# Power_Discrete_-_Core.net
KiCad netlist of a schematic drawn in Altium Designer
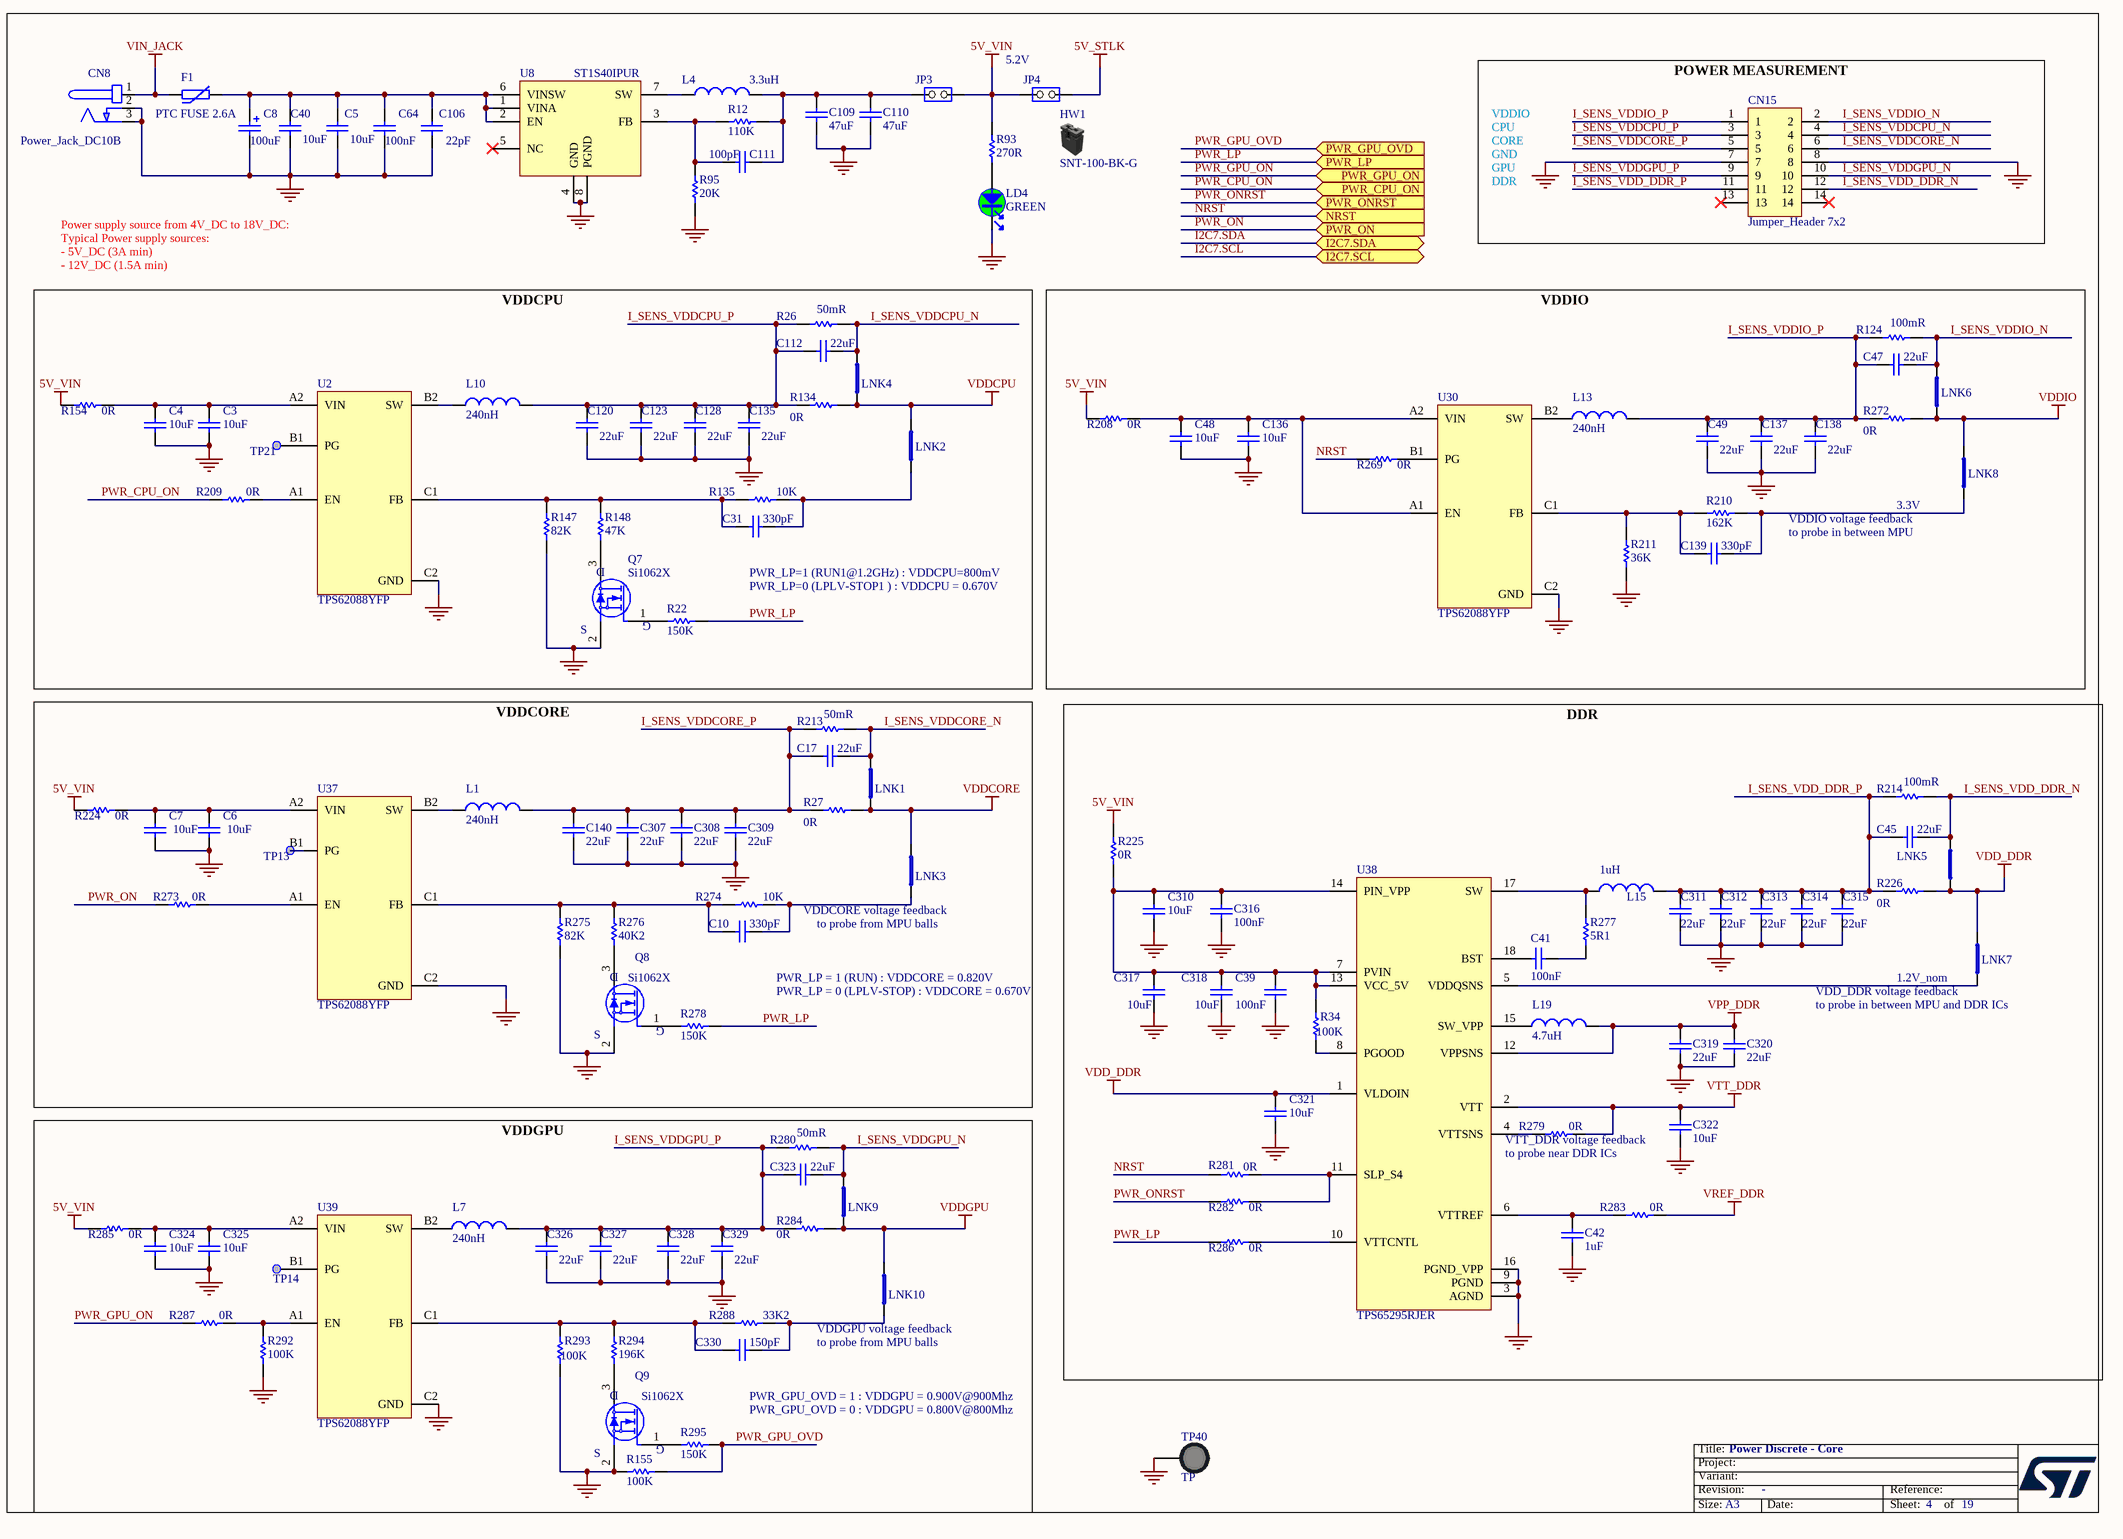
[diagram p0: Power_Discrete - Core.SchDoc]

(export (version "E")
  (design (tool "Eeschema 10.0.6"))
  (components
    (comp (ref "C3")
      (value "10uF")
      (footprint "C0603")
      (description "Capacitor, MLCC, 10uF, 10V, X5R, +/-10%, 0603, T=0,8mm")
      (fields
        (field (name "INTERNAL_PART_NUMBER") "MCD-00099")
        (field (name "MANUFACTURER_PART_NUMBER") "GRM188R61A106KE69D")
      )
      (libsource (lib "MCD_PARTS_database") (part "Capacitor"))
    )
    (comp (ref "C4")
      (value "10uF")
      (footprint "C0603")
      (description "Capacitor, MLCC, 10uF, 10V, X5R, +/-10%, 0603, T=0,8mm")
      (fields
        (field (name "INTERNAL_PART_NUMBER") "MCD-00099")
        (field (name "MANUFACTURER_PART_NUMBER") "GRM188R61A106KE69D")
      )
      (libsource (lib "MCD_PARTS_database") (part "Capacitor"))
    )
    (comp (ref "C5")
      (value "10uF")
      (footprint "C0805")
      (description "Capacitor, MLCC, 10uF, 25V, X5R, +/-10%, 0805, T=0,85mm")
      (fields (field (name "INTERNAL_PART_NUMBER") "MCD-00014") (field (name "MANUFACTURER") "YAGEO"))
      (libsource (lib "MCD_PARTS_database") (part "Capacitor"))
    )
    (comp (ref "C6")
      (value "10uF")
      (footprint "C0603")
      (description "Capacitor, MLCC, 10uF, 10V, X5R, +/-10%, 0603, T=0,8mm")
      (fields
        (field (name "INTERNAL_PART_NUMBER") "MCD-00099")
        (field (name "MANUFACTURER_PART_NUMBER") "GRM188R61A106KE69D")
      )
      (libsource (lib "MCD_PARTS_database") (part "Capacitor"))
    )
    (comp (ref "C7")
      (value "10uF")
      (footprint "C0603")
      (description "Capacitor, MLCC, 10uF, 10V, X5R, +/-10%, 0603, T=0,8mm")
      (fields
        (field (name "INTERNAL_PART_NUMBER") "MCD-00099")
        (field (name "MANUFACTURER_PART_NUMBER") "GRM188R61A106KE69D")
      )
      (libsource (lib "MCD_PARTS_database") (part "Capacitor"))
    )
    (comp (ref "C8")
      (value "100uF")
      (footprint "CPOL_WURTH_WCAP-ASLL_8X10P5")
      (description "Capacitor,Electrolytic,100uF,35V, 20%, SMT, D=8mm, T=10.5mm")
      (fields
        (field (name "INTERNAL_PART_NUMBER") "MCD-01683")
        (field (name "MANUFACTURER") "WURTH ELEKTRONIK")
      )
      (libsource (lib "MCD_PARTS_database") (part "Cap_POL_TANA"))
    )
    (comp (ref "C10")
      (value "330pF")
      (footprint "C0402")
      (description "Capacitor, MLCC, 330pF, 50V, NPO, +/-5%, 0402, T=0.5mm")
      (fields (field (name "INTERNAL_PART_NUMBER") "MCD-01579") (field (name "MANUFACTURER") "YAGEO"))
      (libsource (lib "MCD_PARTS_database") (part "Capacitor"))
    )
    (comp (ref "C17")
      (value "22uF")
      (footprint "C0603")
      (description "Capacitor, MLCC, 22uF, 6V3, X5R, +/-20%, 0603, T=0,8mm")
      (fields
        (field (name "INTERNAL_PART_NUMBER") "MCD-00100")
        (field (name "MANUFACTURER_PART_NUMBER") "GRM188R60J226MEA0J")
      )
      (libsource (lib "MCD_PARTS_database") (part "Capacitor"))
    )
    (comp (ref "C31")
      (value "330pF")
      (footprint "C0402")
      (description "Capacitor, MLCC, 330pF, 50V, NPO, +/-5%, 0402, T=0.5mm")
      (fields (field (name "INTERNAL_PART_NUMBER") "MCD-01579") (field (name "MANUFACTURER") "YAGEO"))
      (libsource (lib "MCD_PARTS_database") (part "Capacitor"))
    )
    (comp (ref "C39")
      (value "100nF")
      (footprint "C0402")
      (description "Capacitor, MLCC, 100nF, 16V, X7R, +/-10%, 0402, T=0.5mm")
      (fields (field (name "INTERNAL_PART_NUMBER") "MCD-00006") (field (name "MANUFACTURER") "YAGEO"))
      (libsource (lib "MCD_PARTS_database") (part "Capacitor"))
    )
    (comp (ref "C40")
      (value "10uF")
      (footprint "C0805")
      (description "Capacitor, MLCC, 10uF, 25V, X5R, +/-10%, 0805, T=0,85mm")
      (fields (field (name "INTERNAL_PART_NUMBER") "MCD-00014") (field (name "MANUFACTURER") "YAGEO"))
      (libsource (lib "MCD_PARTS_database") (part "Capacitor"))
    )
    (comp (ref "C41")
      (value "100nF")
      (footprint "C0402")
      (description "Capacitor, MLCC, 100nF, 16V, X7R, +/-10%, 0402, T=0.5mm")
      (fields (field (name "INTERNAL_PART_NUMBER") "MCD-00006") (field (name "MANUFACTURER") "YAGEO"))
      (libsource (lib "MCD_PARTS_database") (part "Capacitor"))
    )
    (comp (ref "C42")
      (value "1uF")
      (footprint "C0402")
      (description "Capacitor, MLCC, 1uF, 10V, X5R, +/-10%, 0402, T=0.5mm")
      (fields (field (name "INTERNAL_PART_NUMBER") "MCD-01722") (field (name "MANUFACTURER") "YAGEO"))
      (libsource (lib "MCD_PARTS_database") (part "Capacitor"))
    )
    (comp (ref "C45")
      (value "22uF")
      (footprint "C0603")
      (description "Capacitor, MLCC, 22uF, 6V3, X5R, +/-20%, 0603, T=0,8mm")
      (fields
        (field (name "INTERNAL_PART_NUMBER") "MCD-00100")
        (field (name "MANUFACTURER_PART_NUMBER") "GRM188R60J226MEA0J")
      )
      (libsource (lib "MCD_PARTS_database") (part "Capacitor"))
    )
    (comp (ref "C47")
      (value "22uF")
      (footprint "C0603")
      (description "Capacitor, MLCC, 22uF, 6V3, X5R, +/-20%, 0603, T=0,8mm")
      (fields
        (field (name "INTERNAL_PART_NUMBER") "MCD-00100")
        (field (name "MANUFACTURER_PART_NUMBER") "GRM188R60J226MEA0J")
      )
      (libsource (lib "MCD_PARTS_database") (part "Capacitor"))
    )
    (comp (ref "C48")
      (value "10uF")
      (footprint "C0603")
      (description "Capacitor, MLCC, 10uF, 10V, X5R, +/-10%, 0603, T=0,8mm")
      (fields
        (field (name "INTERNAL_PART_NUMBER") "MCD-00099")
        (field (name "MANUFACTURER_PART_NUMBER") "GRM188R61A106KE69D")
      )
      (libsource (lib "MCD_PARTS_database") (part "Capacitor"))
    )
    (comp (ref "C49")
      (value "22uF")
      (footprint "C0603")
      (description "Capacitor, MLCC, 22uF, 6V3, X5R, +/-20%, 0603, T=0,8mm")
      (fields
        (field (name "INTERNAL_PART_NUMBER") "MCD-00100")
        (field (name "MANUFACTURER_PART_NUMBER") "GRM188R60J226MEA0J")
      )
      (libsource (lib "MCD_PARTS_database") (part "Capacitor"))
    )
    (comp (ref "C64")
      (value "100nF")
      (footprint "C0805_H0P85")
      (description "Capacitor, MLCC, 100nF, 50V, X7R, 10%, 0805, T=0,85mm")
      (fields (field (name "INTERNAL_PART_NUMBER") "MCD-01525") (field (name "BMS_PART_NUMBER") "9142249"))
      (libsource (lib "MCD_PARTS_database") (part "Capacitor"))
    )
    (comp (ref "C106")
      (value "22pF")
      (footprint "C0402")
      (description "Capacitor, MLCC, 22pF, 50V, C0G, 5%, 0402, T=0,5mm")
      (fields (field (name "INTERNAL_PART_NUMBER") "MCD-01995") (field (name "MANUFACTURER") "TDK"))
      (libsource (lib "MCD_PARTS_database") (part "Capacitor"))
    )
    (comp (ref "C109")
      (value "47uF")
      (footprint "C0805")
      (description "Capacitor, MLCC, 47uF, 10V, X5R, +/-20%, 0805, T=1,25mm")
      (fields (field (name "INTERNAL_PART_NUMBER") "MCD-00204") (field (name "MANUFACTURER") "MURATA"))
      (libsource (lib "MCD_PARTS_database") (part "Capacitor"))
    )
    (comp (ref "C110")
      (value "47uF")
      (footprint "C0805")
      (description "Capacitor, MLCC, 47uF, 10V, X5R, +/-20%, 0805, T=1,25mm")
      (fields (field (name "INTERNAL_PART_NUMBER") "MCD-00204") (field (name "MANUFACTURER") "MURATA"))
      (libsource (lib "MCD_PARTS_database") (part "Capacitor"))
    )
    (comp (ref "C111")
      (value "100pF")
      (footprint "C0402")
      (description "Capacitor,MLCC,100pF,50V,NPO,+/-5%,0402,T=0,5mm")
      (fields
        (field (name "INTERNAL_PART_NUMBER") "MCD-00205")
        (field (name "MANUFACTURER_PART_NUMBER") "CC0402JRNPO9BN101")
      )
      (libsource (lib "MCD_PARTS_database") (part "Capacitor"))
    )
    (comp (ref "C112")
      (value "22uF")
      (footprint "C0603")
      (description "Capacitor, MLCC, 22uF, 6V3, X5R, +/-20%, 0603, T=0,8mm")
      (fields
        (field (name "INTERNAL_PART_NUMBER") "MCD-00100")
        (field (name "MANUFACTURER_PART_NUMBER") "GRM188R60J226MEA0J")
      )
      (libsource (lib "MCD_PARTS_database") (part "Capacitor"))
    )
    (comp (ref "C120")
      (value "22uF")
      (footprint "C0603")
      (description "Capacitor, MLCC, 22uF, 6V3, X5R, +/-20%, 0603, T=0,8mm")
      (fields
        (field (name "INTERNAL_PART_NUMBER") "MCD-00100")
        (field (name "MANUFACTURER_PART_NUMBER") "GRM188R60J226MEA0J")
      )
      (libsource (lib "MCD_PARTS_database") (part "Capacitor"))
    )
    (comp (ref "C123")
      (value "22uF")
      (footprint "C0603")
      (description "Capacitor, MLCC, 22uF, 6V3, X5R, +/-20%, 0603, T=0,8mm")
      (fields
        (field (name "INTERNAL_PART_NUMBER") "MCD-00100")
        (field (name "MANUFACTURER_PART_NUMBER") "GRM188R60J226MEA0J")
      )
      (libsource (lib "MCD_PARTS_database") (part "Capacitor"))
    )
    (comp (ref "C128")
      (value "22uF")
      (footprint "C0603")
      (description "Capacitor, MLCC, 22uF, 6V3, X5R, +/-20%, 0603, T=0,8mm")
      (fields
        (field (name "INTERNAL_PART_NUMBER") "MCD-00100")
        (field (name "MANUFACTURER_PART_NUMBER") "GRM188R60J226MEA0J")
      )
      (libsource (lib "MCD_PARTS_database") (part "Capacitor"))
    )
    (comp (ref "C135")
      (value "22uF")
      (footprint "C0603")
      (description "Capacitor, MLCC, 22uF, 6V3, X5R, +/-20%, 0603, T=0,8mm")
      (fields
        (field (name "INTERNAL_PART_NUMBER") "MCD-00100")
        (field (name "MANUFACTURER_PART_NUMBER") "GRM188R60J226MEA0J")
      )
      (libsource (lib "MCD_PARTS_database") (part "Capacitor"))
    )
    (comp (ref "C136")
      (value "10uF")
      (footprint "C0603")
      (description "Capacitor, MLCC, 10uF, 10V, X5R, +/-10%, 0603, T=0,8mm")
      (fields
        (field (name "INTERNAL_PART_NUMBER") "MCD-00099")
        (field (name "MANUFACTURER_PART_NUMBER") "GRM188R61A106KE69D")
      )
      (libsource (lib "MCD_PARTS_database") (part "Capacitor"))
    )
    (comp (ref "C137")
      (value "22uF")
      (footprint "C0603")
      (description "Capacitor, MLCC, 22uF, 6V3, X5R, +/-20%, 0603, T=0,8mm")
      (fields
        (field (name "INTERNAL_PART_NUMBER") "MCD-00100")
        (field (name "MANUFACTURER_PART_NUMBER") "GRM188R60J226MEA0J")
      )
      (libsource (lib "MCD_PARTS_database") (part "Capacitor"))
    )
    (comp (ref "C138")
      (value "22uF")
      (footprint "C0603")
      (description "Capacitor, MLCC, 22uF, 6V3, X5R, +/-20%, 0603, T=0,8mm")
      (fields
        (field (name "INTERNAL_PART_NUMBER") "MCD-00100")
        (field (name "MANUFACTURER_PART_NUMBER") "GRM188R60J226MEA0J")
      )
      (libsource (lib "MCD_PARTS_database") (part "Capacitor"))
    )
    (comp (ref "C139")
      (value "330pF")
      (footprint "C0402")
      (description "Capacitor, MLCC, 330pF, 50V, NPO, +/-5%, 0402, T=0.5mm")
      (fields (field (name "INTERNAL_PART_NUMBER") "MCD-01579") (field (name "MANUFACTURER") "YAGEO"))
      (libsource (lib "MCD_PARTS_database") (part "Capacitor"))
    )
    (comp (ref "C140")
      (value "22uF")
      (footprint "C0603")
      (description "Capacitor, MLCC, 22uF, 6V3, X5R, +/-20%, 0603, T=0,8mm")
      (fields (field (name "INTERNAL_PART_NUMBER") "MCD-00100") (field (name "MANUFACTURER") "MURATA"))
      (libsource (lib "MCD_PARTS_database") (part "Capacitor"))
    )
    (comp (ref "C307")
      (value "22uF")
      (footprint "C0603")
      (description "Capacitor, MLCC, 22uF, 6V3, X5R, +/-20%, 0603, T=0,8mm")
      (fields (field (name "INTERNAL_PART_NUMBER") "MCD-00100") (field (name "MANUFACTURER") "MURATA"))
      (libsource (lib "MCD_PARTS_database") (part "Capacitor"))
    )
    (comp (ref "C308")
      (value "22uF")
      (footprint "C0603")
      (description "Capacitor, MLCC, 22uF, 6V3, X5R, +/-20%, 0603, T=0,8mm")
      (fields
        (field (name "INTERNAL_PART_NUMBER") "MCD-00100")
        (field (name "MANUFACTURER_PART_NUMBER") "GRM188R60J226MEA0J")
      )
      (libsource (lib "MCD_PARTS_database") (part "Capacitor"))
    )
    (comp (ref "C309")
      (value "22uF")
      (footprint "C0603")
      (description "Capacitor, MLCC, 22uF, 6V3, X5R, +/-20%, 0603, T=0,8mm")
      (fields
        (field (name "INTERNAL_PART_NUMBER") "MCD-00100")
        (field (name "MANUFACTURER_PART_NUMBER") "GRM188R60J226MEA0J")
      )
      (libsource (lib "MCD_PARTS_database") (part "Capacitor"))
    )
    (comp (ref "C310")
      (value "10uF")
      (footprint "C0603")
      (description "Capacitor, MLCC, 10uF, 10V, X5R, +/-10%, 0603, T=0,8mm")
      (fields
        (field (name "INTERNAL_PART_NUMBER") "MCD-00099")
        (field (name "MANUFACTURER_PART_NUMBER") "GRM188R61A106KE69D")
      )
      (libsource (lib "MCD_PARTS_database") (part "Capacitor"))
    )
    (comp (ref "C311")
      (value "22uF")
      (footprint "C0603")
      (description "Capacitor, MLCC, 22uF, 6V3, X5R, +/-20%, 0603, T=0,8mm")
      (fields
        (field (name "INTERNAL_PART_NUMBER") "MCD-00100")
        (field (name "MANUFACTURER_PART_NUMBER") "GRM188R60J226MEA0J")
      )
      (libsource (lib "MCD_PARTS_database") (part "Capacitor"))
    )
    (comp (ref "C312")
      (value "22uF")
      (footprint "C0603")
      (description "Capacitor, MLCC, 22uF, 6V3, X5R, +/-20%, 0603, T=0,8mm")
      (fields
        (field (name "INTERNAL_PART_NUMBER") "MCD-00100")
        (field (name "MANUFACTURER_PART_NUMBER") "GRM188R60J226MEA0J")
      )
      (libsource (lib "MCD_PARTS_database") (part "Capacitor"))
    )
    (comp (ref "C313")
      (value "22uF")
      (footprint "C0603")
      (description "Capacitor, MLCC, 22uF, 6V3, X5R, +/-20%, 0603, T=0,8mm")
      (fields
        (field (name "INTERNAL_PART_NUMBER") "MCD-00100")
        (field (name "MANUFACTURER_PART_NUMBER") "GRM188R60J226MEA0J")
      )
      (libsource (lib "MCD_PARTS_database") (part "Capacitor"))
    )
    (comp (ref "C314")
      (value "22uF")
      (footprint "C0603")
      (description "Capacitor, MLCC, 22uF, 6V3, X5R, +/-20%, 0603, T=0,8mm")
      (fields
        (field (name "INTERNAL_PART_NUMBER") "MCD-00100")
        (field (name "MANUFACTURER_PART_NUMBER") "GRM188R60J226MEA0J")
      )
      (libsource (lib "MCD_PARTS_database") (part "Capacitor"))
    )
    (comp (ref "C315")
      (value "22uF")
      (footprint "C0603")
      (description "Capacitor, MLCC, 22uF, 6V3, X5R, +/-20%, 0603, T=0,8mm")
      (fields
        (field (name "INTERNAL_PART_NUMBER") "MCD-00100")
        (field (name "MANUFACTURER_PART_NUMBER") "GRM188R60J226MEA0J")
      )
      (libsource (lib "MCD_PARTS_database") (part "Capacitor"))
    )
    (comp (ref "C316")
      (value "100nF")
      (footprint "C0402")
      (description "Capacitor, MLCC, 100nF, 16V, X7R, +/-10%, 0402, T=0.5mm")
      (fields (field (name "INTERNAL_PART_NUMBER") "MCD-00006") (field (name "MANUFACTURER") "YAGEO"))
      (libsource (lib "MCD_PARTS_database") (part "Capacitor"))
    )
    (comp (ref "C317")
      (value "10uF")
      (footprint "C0603")
      (description "Capacitor, MLCC, 10uF, 10V, X5R, +/-10%, 0603, T=0,8mm")
      (fields
        (field (name "INTERNAL_PART_NUMBER") "MCD-00099")
        (field (name "MANUFACTURER_PART_NUMBER") "GRM188R61A106KE69D")
      )
      (libsource (lib "MCD_PARTS_database") (part "Capacitor"))
    )
    (comp (ref "C318")
      (value "10uF")
      (footprint "C0603")
      (description "Capacitor, MLCC, 10uF, 10V, X5R, +/-10%, 0603, T=0,8mm")
      (fields
        (field (name "INTERNAL_PART_NUMBER") "MCD-00099")
        (field (name "MANUFACTURER_PART_NUMBER") "GRM188R61A106KE69D")
      )
      (libsource (lib "MCD_PARTS_database") (part "Capacitor"))
    )
    (comp (ref "C319")
      (value "22uF")
      (footprint "C0603")
      (description "Capacitor, MLCC, 22uF, 6V3, X5R, +/-20%, 0603, T=0,8mm")
      (fields
        (field (name "INTERNAL_PART_NUMBER") "MCD-00100")
        (field (name "MANUFACTURER_PART_NUMBER") "GRM188R60J226MEA0J")
      )
      (libsource (lib "MCD_PARTS_database") (part "Capacitor"))
    )
    (comp (ref "C320")
      (value "22uF")
      (footprint "C0603")
      (description "Capacitor, MLCC, 22uF, 6V3, X5R, +/-20%, 0603, T=0,8mm")
      (fields
        (field (name "INTERNAL_PART_NUMBER") "MCD-00100")
        (field (name "MANUFACTURER_PART_NUMBER") "GRM188R60J226MEA0J")
      )
      (libsource (lib "MCD_PARTS_database") (part "Capacitor"))
    )
    (comp (ref "C321")
      (value "10uF")
      (footprint "C0603")
      (description "Capacitor, MLCC, 10uF, 10V, X5R, +/-10%, 0603, T=0,8mm")
      (fields
        (field (name "INTERNAL_PART_NUMBER") "MCD-00099")
        (field (name "MANUFACTURER_PART_NUMBER") "GRM188R61A106KE69D")
      )
      (libsource (lib "MCD_PARTS_database") (part "Capacitor"))
    )
    (comp (ref "C322")
      (value "10uF")
      (footprint "C0603")
      (description "Capacitor, MLCC, 10uF, 10V, X5R, +/-10%, 0603, T=0,8mm")
      (fields
        (field (name "INTERNAL_PART_NUMBER") "MCD-00099")
        (field (name "MANUFACTURER_PART_NUMBER") "GRM188R61A106KE69D")
      )
      (libsource (lib "MCD_PARTS_database") (part "Capacitor"))
    )
    (comp (ref "C323")
      (value "22uF")
      (footprint "C0603")
      (description "Capacitor, MLCC, 22uF, 6V3, X5R, +/-20%, 0603, T=0,8mm")
      (fields
        (field (name "INTERNAL_PART_NUMBER") "MCD-00100")
        (field (name "MANUFACTURER_PART_NUMBER") "GRM188R60J226MEA0J")
      )
      (libsource (lib "MCD_PARTS_database") (part "Capacitor"))
    )
    (comp (ref "C324")
      (value "10uF")
      (footprint "C0603")
      (description "Capacitor, MLCC, 10uF, 10V, X5R, +/-10%, 0603, T=0,8mm")
      (fields
        (field (name "INTERNAL_PART_NUMBER") "MCD-00099")
        (field (name "MANUFACTURER_PART_NUMBER") "GRM188R61A106KE69D")
      )
      (libsource (lib "MCD_PARTS_database") (part "Capacitor"))
    )
    (comp (ref "C325")
      (value "10uF")
      (footprint "C0603")
      (description "Capacitor, MLCC, 10uF, 10V, X5R, +/-10%, 0603, T=0,8mm")
      (fields
        (field (name "INTERNAL_PART_NUMBER") "MCD-00099")
        (field (name "MANUFACTURER_PART_NUMBER") "GRM188R61A106KE69D")
      )
      (libsource (lib "MCD_PARTS_database") (part "Capacitor"))
    )
    (comp (ref "C326")
      (value "22uF")
      (footprint "C0603")
      (description "Capacitor, MLCC, 22uF, 6V3, X5R, +/-20%, 0603, T=0,8mm")
      (fields
        (field (name "INTERNAL_PART_NUMBER") "MCD-00100")
        (field (name "MANUFACTURER_PART_NUMBER") "GRM188R60J226MEA0J")
      )
      (libsource (lib "MCD_PARTS_database") (part "Capacitor"))
    )
    (comp (ref "C327")
      (value "22uF")
      (footprint "C0603")
      (description "Capacitor, MLCC, 22uF, 6V3, X5R, +/-20%, 0603, T=0,8mm")
      (fields
        (field (name "INTERNAL_PART_NUMBER") "MCD-00100")
        (field (name "MANUFACTURER_PART_NUMBER") "GRM188R60J226MEA0J")
      )
      (libsource (lib "MCD_PARTS_database") (part "Capacitor"))
    )
    (comp (ref "C328")
      (value "22uF")
      (footprint "C0603")
      (description "Capacitor, MLCC, 22uF, 6V3, X5R, +/-20%, 0603, T=0,8mm")
      (fields
        (field (name "INTERNAL_PART_NUMBER") "MCD-00100")
        (field (name "MANUFACTURER_PART_NUMBER") "GRM188R60J226MEA0J")
      )
      (libsource (lib "MCD_PARTS_database") (part "Capacitor"))
    )
    (comp (ref "C329")
      (value "22uF")
      (footprint "C0603")
      (description "Capacitor, MLCC, 22uF, 6V3, X5R, +/-20%, 0603, T=0,8mm")
      (fields
        (field (name "INTERNAL_PART_NUMBER") "MCD-00100")
        (field (name "MANUFACTURER_PART_NUMBER") "GRM188R60J226MEA0J")
      )
      (libsource (lib "MCD_PARTS_database") (part "Capacitor"))
    )
    (comp (ref "C330")
      (value "150pF")
      (footprint "C0402")
      (description "Capacitor, MLCC, 150pF, 50V, NPO, +/-5%, 0402, T=0.5mm")
      (fields (field (name "INTERNAL_PART_NUMBER") "MCD-00672") (field (name "MANUFACTURER") "YAGEO"))
      (libsource (lib "MCD_PARTS_database") (part "Capacitor"))
    )
    (comp (ref "CN8")
      (value "Power_Jack_DC10B")
      (footprint "CON_DC-POWER-SOCKET_CLIFF_FC68149_DC10B")
      (description "DC-Power-Jack, 2.5mm, 5A, RA, TH")
      (fields (field (name "INTERNAL_PART_NUMBER") "MCD-00173") (field (name "BMS_PART_NUMBER") "9087803"))
      (libsource (lib "MCD_PARTS_database") (part "Power_Jack_DC10B"))
    )
    (comp (ref "CN15")
      (value "Jumper_Header 7x2")
      (footprint "CON_SAMTEC_TSW-107-07-X-D")
      (description "Header, 7x2, 2,54mm, VR, TH, Height 5.84mm/2.54mm")
      (fields (field (name "INTERNAL_PART_NUMBER") "MCD-02123") (field (name "MANUFACTURER") "SAMTEC"))
      (libsource (lib "MCD_PARTS_database") (part "Header 7x2"))
    )
    (comp (ref "F1")
      (value "PTC FUSE 2.6A")
      (footprint "PTC_BEL-FUSE_1812_0ZCG0260FF2C")
      (description "SMD, PTC resettable fuse, IH:2.6A, IT:5A, Vdc_max:8V, Rmax:47mohm, BELFUSE")
      (fields (field (name "INTERNAL_PART_NUMBER") "MCD-00624") (field (name "MANUFACTURER") "BELFUSE"))
      (libsource (lib "MCD_PARTS_database") (part "0ZCG0260FF2C"))
    )
    (comp (ref "HW1")
      (value "SNT-100-BK-G")
      (description "SHUNT 2.54mm BLACK")
      (fields (field (name "INTERNAL_PART_NUMBER") "MCD-00043") (field (name "MANUFACTURER") "SAMTEC"))
      (libsource (lib "MCD_PARTS_database") (part "Shunt Black 2.54mm"))
    )
    (comp (ref "JP3")
      (value "Jumper_Header 2x1")
      (footprint "CON_SAMTEC_TSW-102-07-G-S")
      (description "Header, 2x1, 2.54mm, VR, TH, T=5.84mm/2.54mm")
      (fields (field (name "INTERNAL_PART_NUMBER") "MCD-00045") (field (name "MANUFACTURER") "SAMTEC"))
      (libsource (lib "MCD_PARTS_database") (part "Jumper_Header 2x1"))
    )
    (comp (ref "JP4")
      (value "Jumper_Header 2x1")
      (footprint "CON_SAMTEC_TSW-102-07-G-S")
      (description "Header, 2x1, 2.54mm, VR, TH, T=5.84mm/2.54mm")
      (fields (field (name "INTERNAL_PART_NUMBER") "MCD-00045") (field (name "MANUFACTURER") "SAMTEC"))
      (libsource (lib "MCD_PARTS_database") (part "Jumper_Header 2x1"))
    )
    (comp (ref "L1")
      (value "240nH")
      (footprint "IND_MURATA_DFE201612P")
      (description "Inductor, 240nH, +/-20%, 4.4A, 23mR, 0806, T=1.2mm")
      (fields (field (name "INTERNAL_PART_NUMBER") "MCD-02477") (field (name "MANUFACTURER") "MURATA"))
      (libsource (lib "MCD_PARTS_database") (part "Inductor"))
    )
    (comp (ref "L4")
      (value "3.3uH")
      (footprint "IND_5040_WURTH_74404054033")
      (description "Fixed Inductors WE-LQS 5040 3.3uH 3.4A 24mOhm")
      (fields
        (field (name "INTERNAL_PART_NUMBER") "MCD-02220")
        (field (name "MANUFACTURER") "WURTH ELEKTRONIK")
      )
      (libsource (lib "MCD_PARTS_database") (part "Inductor"))
    )
    (comp (ref "L7")
      (value "240nH")
      (footprint "IND_MURATA_DFE201612P")
      (description "Inductor, 240nH, +/-20%, 4.4A, 23mR, 0806, T=1.2mm")
      (fields (field (name "INTERNAL_PART_NUMBER") "MCD-02477") (field (name "MANUFACTURER") "MURATA"))
      (libsource (lib "MCD_PARTS_database") (part "Inductor"))
    )
    (comp (ref "L10")
      (value "240nH")
      (footprint "IND_MURATA_DFE201612P")
      (description "Inductor, 240nH, +/-20%, 4.4A, 23mR, 0806, T=1.2mm")
      (fields (field (name "INTERNAL_PART_NUMBER") "MCD-02477") (field (name "MANUFACTURER") "MURATA"))
      (libsource (lib "MCD_PARTS_database") (part "Inductor"))
    )
    (comp (ref "L13")
      (value "240nH")
      (footprint "IND_MURATA_DFE201612P")
      (description "Inductor, 240nH, +/-20%, 4.4A, 23mR, 0806, T=1.2mm")
      (fields (field (name "INTERNAL_PART_NUMBER") "MCD-02477") (field (name "MANUFACTURER") "MURATA"))
      (libsource (lib "MCD_PARTS_database") (part "Inductor"))
    )
    (comp (ref "L15")
      (value "1uH")
      (footprint "IND_4025_WURTH_74404043010A")
      (description "SMD Power Inductors WE-LQS 1uH 4.9A 14mOhms")
      (fields
        (field (name "INTERNAL_PART_NUMBER") "MCD-01555")
        (field (name "MANUFACTURER_PART_NUMBER") "74404043010A")
      )
      (libsource (lib "MCD_PARTS_database") (part "Inductor"))
    )
    (comp (ref "L19")
      (value "4.7uH")
      (footprint "IND_4025_WURTH_74404043047A")
      (description "Inductor, 4.7uH, +/-20%, 4.9A, 0R014, 4x4mm, T=2.5mm")
      (fields
        (field (name "INTERNAL_PART_NUMBER") "MCD-02490")
        (field (name "MANUFACTURER") "WURTH ELEKTRONIK")
      )
      (libsource (lib "MCD_PARTS_database") (part "Inductor"))
    )
    (comp (ref "LD4")
      (value "GREEN")
      (footprint "LED_0603_OSRAM_LG-Q396-PS-35_GREEN_1A2K_H0P4")
      (description "LED Green, 0603 SMD, Forward Voltage Typ=2V, Max=2.5V")
      (fields
        (field (name "INTERNAL_PART_NUMBER") "MCD-00588")
        (field (name "MANUFACTURER_PART_NUMBER") "LG Q396-PS-35")
        (field (name "PROVIDED_BY") "SUBCO")
      )
      (libsource (lib "MCD_PARTS_database") (part "LED_green"))
    )
    (comp (ref "LNK1")
      (value "link_200")
      (footprint "LINK200")
      (description "link 0.2mm")
      (libsource (lib "MCD_Temp_LBE") (part "link_200"))
    )
    (comp (ref "LNK2")
      (value "link_200")
      (footprint "LINK200")
      (description "link 0.2mm")
      (libsource (lib "MCD_Temp_LBE") (part "link_200"))
    )
    (comp (ref "LNK3")
      (value "link_200")
      (footprint "LINK200")
      (description "link 0.2mm")
      (libsource (lib "MCD_Temp_LBE") (part "link_200"))
    )
    (comp (ref "LNK4")
      (value "link_200")
      (footprint "LINK200")
      (description "link 0.2mm")
      (libsource (lib "MCD_Temp_LBE") (part "link_200"))
    )
    (comp (ref "LNK5")
      (value "link_200")
      (footprint "LINK200")
      (description "link 0.2mm")
      (libsource (lib "MCD_Temp_LBE") (part "link_200"))
    )
    (comp (ref "LNK6")
      (value "link_200")
      (footprint "LINK200")
      (description "link 0.2mm")
      (libsource (lib "MCD_Temp_LBE") (part "link_200"))
    )
    (comp (ref "LNK7")
      (value "link_200")
      (footprint "LINK200")
      (description "link 0.2mm")
      (libsource (lib "MCD_Temp_LBE") (part "link_200"))
    )
    (comp (ref "LNK8")
      (value "link_200")
      (footprint "LINK200")
      (description "link 0.2mm")
      (libsource (lib "MCD_Temp_LBE") (part "link_200"))
    )
    (comp (ref "LNK9")
      (value "link_200")
      (footprint "LINK200")
      (description "link 0.2mm")
      (libsource (lib "MCD_Temp_LBE") (part "link_200"))
    )
    (comp (ref "LNK10")
      (value "link_200")
      (footprint "LINK200")
      (description "link 0.2mm")
      (libsource (lib "MCD_Temp_LBE") (part "link_200"))
    )
    (comp (ref "Q7")
      (value "Si1062X")
      (footprint "MOS_SC89-3L")
      (description "MOSFET N-CH 20V SC-89")
      (fields (field (name "INTERNAL_PART_NUMBER") "MCD-02221") (field (name "MANUFACTURER") "VISHAY"))
      (libsource (lib "MCD_PARTS_database") (part "MOSFET_N-CHANNEL"))
    )
    (comp (ref "Q8")
      (value "Si1062X")
      (footprint "MOS_SC89-3L")
      (description "MOSFET N-CH 20V SC-89")
      (fields (field (name "INTERNAL_PART_NUMBER") "MCD-02221") (field (name "MANUFACTURER") "VISHAY"))
      (libsource (lib "MCD_PARTS_database") (part "MOSFET_N-CHANNEL"))
    )
    (comp (ref "Q9")
      (value "Si1062X")
      (footprint "MOS_SC89-3L")
      (description "MOSFET N-CH 20V SC-89")
      (fields (field (name "INTERNAL_PART_NUMBER") "MCD-02221") (field (name "MANUFACTURER") "VISHAY"))
      (libsource (lib "MCD_PARTS_database") (part "MOSFET_N-CHANNEL"))
    )
    (comp (ref "R12")
      (value "110K")
      (footprint "R0402")
      (description "Resistor,110K,0402,1%,1/16W")
      (fields
        (field (name "INTERNAL_PART_NUMBER") "MCD-00367")
        (field (name "MANUFACTURER_PART_NUMBER") "RC0402FR-07110KL")
      )
      (libsource (lib "MCD_PARTS_database") (part "Resistor"))
    )
    (comp (ref "R22")
      (value "150K")
      (footprint "R0402")
      (description "Resistor,150K,0402,1%,1/16W")
      (fields
        (field (name "INTERNAL_PART_NUMBER") "MCD-00165")
        (field (name "MANUFACTURER_PART_NUMBER") "RC0402FR-07150KL")
      )
      (libsource (lib "MCD_PARTS_database") (part "Resistor"))
    )
    (comp (ref "R26")
      (value "50mR")
      (footprint "R0603")
      (description "Resistor,50moHm,0603,1%,1/3W, T=0.55mm")
      (fields (field (name "INTERNAL_PART_NUMBER") "MCD-02233") (field (name "MANUFACTURER") "PANASONIC"))
      (libsource (lib "MCD_PARTS_database") (part "Resistor"))
    )
    (comp (ref "R27")
      (value "0R")
      (footprint "R0603")
      (description "Resistor,0R,0603,ULO")
      (fields
        (field (name "INTERNAL_PART_NUMBER") "MCD-00181")
        (field (name "MANUFACTURER_PART_NUMBER") "PMR03EZPJ000")
        (field (name "PROVIDED_BY") "SUBCO")
      )
      (libsource (lib "MCD_PARTS_database") (part "Resistor"))
    )
    (comp (ref "R34")
      (value "100K")
      (footprint "R0402")
      (description "Resistor,100K,0402,1%,1/16W")
      (fields (field (name "INTERNAL_PART_NUMBER") "MCD-00059") (field (name "MANUFACTURER") "YAGEO"))
      (libsource (lib "MCD_PARTS_database") (part "Resistor"))
    )
    (comp (ref "R93")
      (value "270R")
      (footprint "R0402")
      (description "Resistor,270R,0402,1%,1/16W")
      (fields
        (field (name "INTERNAL_PART_NUMBER") "MCD-00441")
        (field (name "MANUFACTURER_PART_NUMBER") "RC0402FR-07270RL")
        (field (name "PROVIDED_BY") "SUBCO")
      )
      (libsource (lib "MCD_PARTS_database") (part "Resistor"))
    )
    (comp (ref "R95")
      (value "20K")
      (footprint "R0402")
      (description "Resistor,20K,0402,1%,1/16W")
      (fields (field (name "INTERNAL_PART_NUMBER") "MCD-00421") (field (name "MANUFACTURER") "YAGEO"))
      (libsource (lib "MCD_PARTS_database") (part "Resistor"))
    )
    (comp (ref "R124")
      (value "100mR")
      (footprint "R0603")
      (description "Resistor,100moHm,0603,1%,1/3W")
      (fields (field (name "INTERNAL_PART_NUMBER") "MCD-02234") (field (name "MANUFACTURER") "PANASONIC"))
      (libsource (lib "MCD_PARTS_database") (part "Resistor"))
    )
    (comp (ref "R134")
      (value "0R")
      (footprint "R0603")
      (description "Resistor,0R,0603,ULO")
      (fields
        (field (name "INTERNAL_PART_NUMBER") "MCD-00181")
        (field (name "MANUFACTURER_PART_NUMBER") "PMR03EZPJ000")
        (field (name "PROVIDED_BY") "SUBCO")
      )
      (libsource (lib "MCD_PARTS_database") (part "Resistor"))
    )
    (comp (ref "R135")
      (value "10K")
      (footprint "R0402")
      (description "Resistor,10K,0402,1%,1/16W")
      (fields (field (name "INTERNAL_PART_NUMBER") "MCD-00053") (field (name "BMS_PART_NUMBER") "9131590"))
      (libsource (lib "MCD_PARTS_database") (part "Resistor"))
    )
    (comp (ref "R147")
      (value "82K")
      (footprint "R0402")
      (description "Resistor, 82K, 0402, +/-1%, 1/16W")
      (fields (field (name "INTERNAL_PART_NUMBER") "MCD-00531") (field (name "MANUFACTURER") "YAGEO"))
      (libsource (lib "MCD_PARTS_database") (part "Resistor"))
    )
    (comp (ref "R148")
      (value "47K")
      (footprint "R0402")
      (description "Resistor, 47K, 0402, +/-1%, 1/16W")
      (fields (field (name "INTERNAL_PART_NUMBER") "MCD-00063") (field (name "MANUFACTURER") "YAGEO"))
      (libsource (lib "MCD_PARTS_database") (part "Resistor"))
    )
    (comp (ref "R154")
      (value "0R")
      (footprint "R0603")
      (description "Resistor,0R,0603,5%,1/10W")
      (fields
        (field (name "INTERNAL_PART_NUMBER") "MCD-00056")
        (field (name "MANUFACTURER_PART_NUMBER") "RC0603JR-070RL")
      )
      (libsource (lib "MCD_PARTS_database") (part "Resistor"))
    )
    (comp (ref "R155")
      (value "100K")
      (footprint "R0402")
      (description "Resistor, 100K, 0402, +/-1%, 1/16W")
      (fields (field (name "INTERNAL_PART_NUMBER") "MCD-00059") (field (name "MANUFACTURER") "YAGEO"))
      (libsource (lib "MCD_PARTS_database") (part "Resistor"))
    )
    (comp (ref "R208")
      (value "0R")
      (footprint "R0603")
      (description "Resistor,0R,0603,5%,1/10W")
      (fields
        (field (name "INTERNAL_PART_NUMBER") "MCD-00056")
        (field (name "MANUFACTURER_PART_NUMBER") "RC0603JR-070RL")
      )
      (libsource (lib "MCD_PARTS_database") (part "Resistor"))
    )
    (comp (ref "R209")
      (value "0R")
      (footprint "R0402")
      (description "Resistor,0R,0402,5%,1/16W")
      (fields
        (field (name "INTERNAL_PART_NUMBER") "MCD-00052")
        (field (name "MANUFACTURER_PART_NUMBER") "RC0402JR-070RL")
      )
      (libsource (lib "MCD_PARTS_database") (part "Resistor"))
    )
    (comp (ref "R210")
      (value "162K")
      (footprint "R0402")
      (description "Resistor,162K,0402,1%,1/16W")
      (fields (field (name "INTERNAL_PART_NUMBER") "MCD-02482") (field (name "MANUFACTURER") "YAGEO"))
      (libsource (lib "MCD_PARTS_database") (part "Resistor"))
    )
    (comp (ref "R211")
      (value "36K")
      (footprint "R0402")
      (description "Resistor, 36K, 0402, 1%, 1/16W")
      (fields (field (name "INTERNAL_PART_NUMBER") "MCD-00069") (field (name "MANUFACTURER") "YAGEO"))
      (libsource (lib "MCD_PARTS_database") (part "Resistor"))
    )
    (comp (ref "R213")
      (value "50mR")
      (footprint "R0603")
      (description "Resistor,50moHm,0603,1%,1/3W, T=0.55mm")
      (fields (field (name "INTERNAL_PART_NUMBER") "MCD-02233") (field (name "MANUFACTURER") "PANASONIC"))
      (libsource (lib "MCD_PARTS_database") (part "Resistor"))
    )
    (comp (ref "R214")
      (value "100mR")
      (footprint "R0603")
      (description "Resistor,100moHm,0603,1%,1/3W")
      (fields (field (name "INTERNAL_PART_NUMBER") "MCD-02234") (field (name "MANUFACTURER") "PANASONIC"))
      (libsource (lib "MCD_PARTS_database") (part "Resistor"))
    )
    (comp (ref "R224")
      (value "0R")
      (footprint "R0603")
      (description "Resistor,0R,0603,5%,1/10W")
      (fields
        (field (name "INTERNAL_PART_NUMBER") "MCD-00056")
        (field (name "MANUFACTURER_PART_NUMBER") "RC0603JR-070RL")
      )
      (libsource (lib "MCD_PARTS_database") (part "Resistor"))
    )
    (comp (ref "R225")
      (value "0R")
      (footprint "R0603")
      (description "Resistor,0R,0603,5%,1/10W")
      (fields
        (field (name "INTERNAL_PART_NUMBER") "MCD-00056")
        (field (name "MANUFACTURER_PART_NUMBER") "RC0603JR-070RL")
      )
      (libsource (lib "MCD_PARTS_database") (part "Resistor"))
    )
    (comp (ref "R226")
      (value "0R")
      (footprint "R0603")
      (description "Resistor,0R,0603,ULO")
      (fields
        (field (name "INTERNAL_PART_NUMBER") "MCD-00181")
        (field (name "MANUFACTURER_PART_NUMBER") "PMR03EZPJ000")
        (field (name "PROVIDED_BY") "SUBCO")
      )
      (libsource (lib "MCD_PARTS_database") (part "Resistor"))
    )
    (comp (ref "R269")
      (value "0R")
      (footprint "R0603")
      (description "Resistor,0R,0603,5%,1/10W")
      (fields
        (field (name "INTERNAL_PART_NUMBER") "MCD-00056")
        (field (name "MANUFACTURER_PART_NUMBER") "RC0603JR-070RL")
      )
      (libsource (lib "MCD_PARTS_database") (part "Resistor"))
    )
    (comp (ref "R272")
      (value "0R")
      (footprint "R0603")
      (description "Resistor,0R,0603,ULO")
      (fields
        (field (name "INTERNAL_PART_NUMBER") "MCD-00181")
        (field (name "MANUFACTURER_PART_NUMBER") "PMR03EZPJ000")
        (field (name "PROVIDED_BY") "SUBCO")
      )
      (libsource (lib "MCD_PARTS_database") (part "Resistor"))
    )
    (comp (ref "R273")
      (value "0R")
      (footprint "R0402")
      (description "Resistor,0R,0402,5%,1/16W")
      (fields
        (field (name "INTERNAL_PART_NUMBER") "MCD-00052")
        (field (name "MANUFACTURER_PART_NUMBER") "RC0402JR-070RL")
      )
      (libsource (lib "MCD_PARTS_database") (part "Resistor"))
    )
    (comp (ref "R274")
      (value "10K")
      (footprint "R0402")
      (description "Resistor,10K,0402,1%,1/16W")
      (fields (field (name "INTERNAL_PART_NUMBER") "MCD-00053") (field (name "BMS_PART_NUMBER") "9131590"))
      (libsource (lib "MCD_PARTS_database") (part "Resistor"))
    )
    (comp (ref "R275")
      (value "82K")
      (footprint "R0402")
      (description "Resistor, 82K, 0402, +/-1%, 1/16W")
      (fields (field (name "INTERNAL_PART_NUMBER") "MCD-00531") (field (name "MANUFACTURER") "YAGEO"))
      (libsource (lib "MCD_PARTS_database") (part "Resistor"))
    )
    (comp (ref "R276")
      (value "40K2")
      (footprint "R0402")
      (description "Resistor, 40K2, 0402, +/-1%, 1/16W")
      (fields (field (name "INTERNAL_PART_NUMBER") "MCD-02479") (field (name "MANUFACTURER") "YAGEO"))
      (libsource (lib "MCD_PARTS_database") (part "Resistor"))
    )
    (comp (ref "R277")
      (value "5R1")
      (footprint "R0402")
      (description "Resistor, 5R1, 0402, +/-1%, 1/16W")
      (fields (field (name "INTERNAL_PART_NUMBER") "MCD-01516") (field (name "MANUFACTURER") "YAGEO"))
      (libsource (lib "MCD_PARTS_database") (part "Resistor"))
    )
    (comp (ref "R278")
      (value "150K")
      (footprint "R0402")
      (description "Resistor,150K,0402,1%,1/16W")
      (fields
        (field (name "INTERNAL_PART_NUMBER") "MCD-00165")
        (field (name "MANUFACTURER_PART_NUMBER") "RC0402FR-07150KL")
      )
      (libsource (lib "MCD_PARTS_database") (part "Resistor"))
    )
    (comp (ref "R279")
      (value "0R")
      (footprint "R0402")
      (description "Resistor,0R,0402,5%,1/16W")
      (fields
        (field (name "INTERNAL_PART_NUMBER") "MCD-00052")
        (field (name "MANUFACTURER_PART_NUMBER") "RC0402JR-070RL")
      )
      (libsource (lib "MCD_PARTS_database") (part "Resistor"))
    )
    (comp (ref "R280")
      (value "50mR")
      (footprint "R0603")
      (description "Resistor,50moHm,0603,1%,1/3W, T=0.55mm")
      (fields (field (name "INTERNAL_PART_NUMBER") "MCD-02233") (field (name "MANUFACTURER") "PANASONIC"))
      (libsource (lib "MCD_PARTS_database") (part "Resistor"))
    )
    (comp (ref "R281")
      (value "0R")
      (footprint "R0402")
      (description "Resistor,0R,0402,5%,1/16W")
      (fields
        (field (name "INTERNAL_PART_NUMBER") "MCD-00052")
        (field (name "MANUFACTURER_PART_NUMBER") "RC0402JR-070RL")
      )
      (libsource (lib "MCD_PARTS_database") (part "Resistor"))
    )
    (comp (ref "R282")
      (value "0R")
      (footprint "R0402")
      (description "Resistor,0R,0402,5%,1/16W")
      (fields
        (field (name "INTERNAL_PART_NUMBER") "MCD-00052")
        (field (name "MANUFACTURER_PART_NUMBER") "RC0402JR-070RL")
      )
      (libsource (lib "MCD_PARTS_database") (part "Resistor"))
    )
    (comp (ref "R283")
      (value "0R")
      (footprint "R0402")
      (description "Resistor,0R,0402,5%,1/16W")
      (fields
        (field (name "INTERNAL_PART_NUMBER") "MCD-00052")
        (field (name "MANUFACTURER_PART_NUMBER") "RC0402JR-070RL")
      )
      (libsource (lib "MCD_PARTS_database") (part "Resistor"))
    )
    (comp (ref "R284")
      (value "0R")
      (footprint "R0603")
      (description "Resistor,0R,0603,ULO")
      (fields
        (field (name "INTERNAL_PART_NUMBER") "MCD-00181")
        (field (name "MANUFACTURER_PART_NUMBER") "PMR03EZPJ000")
        (field (name "PROVIDED_BY") "SUBCO")
      )
      (libsource (lib "MCD_PARTS_database") (part "Resistor"))
    )
    (comp (ref "R285")
      (value "0R")
      (footprint "R0603")
      (description "Resistor,0R,0603,5%,1/10W")
      (fields
        (field (name "INTERNAL_PART_NUMBER") "MCD-00056")
        (field (name "MANUFACTURER_PART_NUMBER") "RC0603JR-070RL")
      )
      (libsource (lib "MCD_PARTS_database") (part "Resistor"))
    )
    (comp (ref "R286")
      (value "0R")
      (footprint "R0402")
      (description "Resistor,0R,0402,5%,1/16W")
      (fields
        (field (name "INTERNAL_PART_NUMBER") "MCD-00052")
        (field (name "MANUFACTURER_PART_NUMBER") "RC0402JR-070RL")
      )
      (libsource (lib "MCD_PARTS_database") (part "Resistor"))
    )
    (comp (ref "R287")
      (value "0R")
      (footprint "R0402")
      (description "Resistor,0R,0402,5%,1/16W")
      (fields
        (field (name "INTERNAL_PART_NUMBER") "MCD-00052")
        (field (name "MANUFACTURER_PART_NUMBER") "RC0402JR-070RL")
      )
      (libsource (lib "MCD_PARTS_database") (part "Resistor"))
    )
    (comp (ref "R288")
      (value "33K2")
      (footprint "R0402")
      (description "Resistor, 33K2, 0402, +/-1%, 1/16W")
      (fields (field (name "INTERNAL_PART_NUMBER") "MCD-02480") (field (name "MANUFACTURER") "YAGEO"))
      (libsource (lib "MCD_PARTS_database") (part "Resistor"))
    )
    (comp (ref "R292")
      (value "100K")
      (footprint "R0402")
      (description "Resistor, 100K, 0402, +/-1%, 1/16W")
      (fields (field (name "INTERNAL_PART_NUMBER") "MCD-00059") (field (name "MANUFACTURER") "YAGEO"))
      (libsource (lib "MCD_PARTS_database") (part "Resistor"))
    )
    (comp (ref "R293")
      (value "100K")
      (footprint "R0402")
      (description "Resistor, 100K, 0402, +/-1%, 1/16W")
      (fields (field (name "INTERNAL_PART_NUMBER") "MCD-00059") (field (name "MANUFACTURER") "YAGEO"))
      (libsource (lib "MCD_PARTS_database") (part "Resistor"))
    )
    (comp (ref "R294")
      (value "196K")
      (footprint "R0402")
      (description "Resistor, 196K, 0402, +/-1%, 1/16W")
      (fields (field (name "INTERNAL_PART_NUMBER") "MCD-02481") (field (name "MANUFACTURER") "YAGEO"))
      (libsource (lib "MCD_PARTS_database") (part "Resistor"))
    )
    (comp (ref "R295")
      (value "150K")
      (footprint "R0402")
      (description "Resistor,150K,0402,1%,1/16W")
      (fields
        (field (name "INTERNAL_PART_NUMBER") "MCD-00165")
        (field (name "MANUFACTURER_PART_NUMBER") "RC0402FR-07150KL")
      )
      (libsource (lib "MCD_PARTS_database") (part "Resistor"))
    )
    (comp (ref "TP13")
      (value "Test Point")
      (footprint "TP_SMD_0-6MM")
      (description "Test Point 0.6mm")
      (fields (field (name "INTERNAL_PART_NUMBER") "MCD-00631"))
      (libsource (lib "MCD_PARTS_database") (part "Test Point"))
    )
    (comp (ref "TP14")
      (value "Test Point")
      (footprint "TP_SMD_0-6MM")
      (description "Test Point 0.6mm")
      (fields (field (name "INTERNAL_PART_NUMBER") "MCD-00631"))
      (libsource (lib "MCD_PARTS_database") (part "Test Point"))
    )
    (comp (ref "TP21")
      (value "Test Point")
      (footprint "TP_SMD_0-6MM")
      (description "Test Point 0.6mm")
      (fields (field (name "INTERNAL_PART_NUMBER") "MCD-00631"))
      (libsource (lib "MCD_PARTS_database") (part "Test Point"))
    )
    (comp (ref "TP40")
      (value "TP")
      (footprint "TP_PTH-1P02MM_TEST-TERMINAL_RS_101-2391_BLACK")
      (description "Vero Technologies 1.02mm Black Terminal Post")
      (fields
        (field (name "INTERNAL_PART_NUMBER") "MCD-00713")
        (field (name "MANUFACTURER_PART_NUMBER") "20-2137")
      )
      (libsource (lib "MCD_PARTS_database") (part "Test_pin_conn_black"))
    )
    (comp (ref "U2")
      (value "TPS62088YFP")
      (footprint "ICC_DSBGA6_YFP_0P80X1P20_H0P50_P040")
      (description "Adjustable Step down converter 3A , output 0.6V to 4V")
      (fields
        (field (name "INTERNAL_PART_NUMBER") "MCD-02469")
        (field (name "MANUFACTURER") "TEXAS INSTRUMENTS")
      )
      (libsource (lib "MCD_PARTS_database") (part "TPS62088YFP"))
    )
    (comp (ref "U8")
      (value "ST1S40IPUR")
      (footprint "ICC_VFQFPN8-EPAD_4X4_P080")
      (description "3 A DC step-down switching regulator")
      (fields
        (field (name "INTERNAL_PART_NUMBER") "MCD-02219")
        (field (name "MANUFACTURER") "STMICROELECTRONICS")
      )
      (libsource (lib "MCD_PARTS_database") (part "ST1S40IPUR"))
    )
    (comp (ref "U30")
      (value "TPS62088YFP")
      (footprint "ICC_DSBGA6_YFP_0P80X1P20_H0P50_P040")
      (description "Adjustable Step down converter 3A , output 0.6V to 4V")
      (fields
        (field (name "INTERNAL_PART_NUMBER") "MCD-02469")
        (field (name "MANUFACTURER") "TEXAS INSTRUMENTS")
      )
      (libsource (lib "MCD_PARTS_database") (part "TPS62088YFP"))
    )
    (comp (ref "U37")
      (value "TPS62088YFP")
      (footprint "ICC_DSBGA6_YFP_0P80X1P20_H0P50_P040")
      (description "Adjustable Step down converter 3A , output 0.6V to 4V")
      (fields
        (field (name "INTERNAL_PART_NUMBER") "MCD-02469")
        (field (name "MANUFACTURER") "TEXAS INSTRUMENTS")
      )
      (libsource (lib "MCD_PARTS_database") (part "TPS62088YFP"))
    )
    (comp (ref "U38")
      (value "TPS65295RJER")
      (footprint "ICC_VQFN18_3X3_P050")
      (description "Complete Power solution for DDR4 , VQFN , 3 x 3 mm")
      (fields
        (field (name "INTERNAL_PART_NUMBER") "MCD-02369")
        (field (name "MANUFACTURER") "TEXAS INSTRUMENTS")
      )
      (libsource (lib "MCD_PARTS_database") (part "TPS65295"))
    )
    (comp (ref "U39")
      (value "TPS62088YFP")
      (footprint "ICC_DSBGA6_YFP_0P80X1P20_H0P50_P040")
      (description "Adjustable Step down converter 3A , output 0.6V to 4V")
      (fields
        (field (name "INTERNAL_PART_NUMBER") "MCD-02469")
        (field (name "MANUFACTURER") "TEXAS INSTRUMENTS")
      )
      (libsource (lib "MCD_PARTS_database") (part "TPS62088YFP"))
    )
  )
  (nets
    (net (code "3") (name "/I_SENS_VDDCORE_N") (class "Default")
      (node (ref "C17") (pin "1") (pinfunction "1_1") (pintype "passive"))
      (node (ref "CN15") (pin "6") (pinfunction "6_6") (pintype "passive"))
      (node (ref "LNK1") (pin "2") (pinfunction "2_2") (pintype "passive"))
      (node (ref "R213") (pin "2") (pinfunction "2_2") (pintype "passive"))
    )
    (net (code "4") (name "/I_SENS_VDDCORE_P") (class "Default")
      (node (ref "C140") (pin "2") (pinfunction "2_2") (pintype "passive"))
      (node (ref "C17") (pin "2") (pinfunction "2_2") (pintype "passive"))
      (node (ref "C307") (pin "2") (pinfunction "2_2") (pintype "passive"))
      (node (ref "C308") (pin "2") (pinfunction "2_2") (pintype "passive"))
      (node (ref "C309") (pin "2") (pinfunction "2_2") (pintype "passive"))
      (node (ref "CN15") (pin "5") (pinfunction "5_5") (pintype "passive"))
      (node (ref "L1") (pin "2") (pinfunction "2_2") (pintype "passive"))
      (node (ref "R213") (pin "1") (pinfunction "1_1") (pintype "passive"))
      (node (ref "R27") (pin "1") (pinfunction "1_1") (pintype "passive"))
    )
    (net (code "5") (name "/I_SENS_VDDCPU_N") (class "Default")
      (node (ref "C112") (pin "1") (pinfunction "1_1") (pintype "passive"))
      (node (ref "CN15") (pin "4") (pinfunction "4_4") (pintype "passive"))
      (node (ref "LNK4") (pin "2") (pinfunction "2_2") (pintype "passive"))
      (node (ref "R26") (pin "2") (pinfunction "2_2") (pintype "passive"))
    )
    (net (code "6") (name "/I_SENS_VDDCPU_P") (class "Default")
      (node (ref "C112") (pin "2") (pinfunction "2_2") (pintype "passive"))
      (node (ref "C120") (pin "2") (pinfunction "2_2") (pintype "passive"))
      (node (ref "C123") (pin "2") (pinfunction "2_2") (pintype "passive"))
      (node (ref "C128") (pin "2") (pinfunction "2_2") (pintype "passive"))
      (node (ref "C135") (pin "2") (pinfunction "2_2") (pintype "passive"))
      (node (ref "CN15") (pin "3") (pinfunction "3_3") (pintype "passive"))
      (node (ref "L10") (pin "2") (pinfunction "2_2") (pintype "passive"))
      (node (ref "R134") (pin "1") (pinfunction "1_1") (pintype "passive"))
      (node (ref "R26") (pin "1") (pinfunction "1_1") (pintype "passive"))
    )
    (net (code "7") (name "/I_SENS_VDDGPU_N") (class "Default")
      (node (ref "C323") (pin "1") (pinfunction "1_1") (pintype "passive"))
      (node (ref "CN15") (pin "10") (pinfunction "10_10") (pintype "passive"))
      (node (ref "LNK9") (pin "2") (pinfunction "2_2") (pintype "passive"))
      (node (ref "R280") (pin "2") (pinfunction "2_2") (pintype "passive"))
    )
    (net (code "8") (name "/I_SENS_VDDGPU_P") (class "Default")
      (node (ref "C323") (pin "2") (pinfunction "2_2") (pintype "passive"))
      (node (ref "C326") (pin "2") (pinfunction "2_2") (pintype "passive"))
      (node (ref "C327") (pin "2") (pinfunction "2_2") (pintype "passive"))
      (node (ref "C328") (pin "2") (pinfunction "2_2") (pintype "passive"))
      (node (ref "C329") (pin "2") (pinfunction "2_2") (pintype "passive"))
      (node (ref "CN15") (pin "9") (pinfunction "9_9") (pintype "passive"))
      (node (ref "L7") (pin "2") (pinfunction "2_2") (pintype "passive"))
      (node (ref "R280") (pin "1") (pinfunction "1_1") (pintype "passive"))
      (node (ref "R284") (pin "1") (pinfunction "1_1") (pintype "passive"))
    )
    (net (code "9") (name "/I_SENS_VDDIO_N") (class "Default")
      (node (ref "C47") (pin "1") (pinfunction "1_1") (pintype "passive"))
      (node (ref "CN15") (pin "2") (pinfunction "2_2") (pintype "passive"))
      (node (ref "LNK6") (pin "1") (pinfunction "1_1") (pintype "passive"))
      (node (ref "R124") (pin "2") (pinfunction "2_2") (pintype "passive"))
    )
    (net (code "10") (name "/I_SENS_VDDIO_P") (class "Default")
      (node (ref "C137") (pin "2") (pinfunction "2_2") (pintype "passive"))
      (node (ref "C138") (pin "2") (pinfunction "2_2") (pintype "passive"))
      (node (ref "C47") (pin "2") (pinfunction "2_2") (pintype "passive"))
      (node (ref "C49") (pin "2") (pinfunction "2_2") (pintype "passive"))
      (node (ref "CN15") (pin "1") (pinfunction "1_1") (pintype "passive"))
      (node (ref "L13") (pin "2") (pinfunction "2_2") (pintype "passive"))
      (node (ref "R124") (pin "1") (pinfunction "1_1") (pintype "passive"))
      (node (ref "R272") (pin "1") (pinfunction "1_1") (pintype "passive"))
    )
    (net (code "11") (name "/I_SENS_VDD_DDR_N") (class "Default")
      (node (ref "C45") (pin "1") (pinfunction "1_1") (pintype "passive"))
      (node (ref "CN15") (pin "12") (pinfunction "12_12") (pintype "passive"))
      (node (ref "LNK5") (pin "1") (pinfunction "1_1") (pintype "passive"))
      (node (ref "R214") (pin "2") (pinfunction "2_2") (pintype "passive"))
    )
    (net (code "12") (name "/I_SENS_VDD_DDR_P") (class "Default")
      (node (ref "C311") (pin "2") (pinfunction "2_2") (pintype "passive"))
      (node (ref "C312") (pin "2") (pinfunction "2_2") (pintype "passive"))
      (node (ref "C313") (pin "2") (pinfunction "2_2") (pintype "passive"))
      (node (ref "C314") (pin "2") (pinfunction "2_2") (pintype "passive"))
      (node (ref "C315") (pin "2") (pinfunction "2_2") (pintype "passive"))
      (node (ref "C45") (pin "2") (pinfunction "2_2") (pintype "passive"))
      (node (ref "CN15") (pin "11") (pinfunction "11_11") (pintype "passive"))
      (node (ref "L15") (pin "2") (pinfunction "2_2") (pintype "passive"))
      (node (ref "R214") (pin "1") (pinfunction "1_1") (pintype "passive"))
      (node (ref "R226") (pin "1") (pinfunction "1_1") (pintype "passive"))
    )
    (net (code "13") (name "/NRST") (class "Default")
      (node (ref "R269") (pin "1") (pinfunction "1_1") (pintype "passive"))
      (node (ref "R281") (pin "1") (pinfunction "1_1") (pintype "passive"))
    )
    (net (code "14") (name "/PWR_CPU_ON") (class "Default")
      (node (ref "R209") (pin "1") (pinfunction "1_1") (pintype "passive"))
    )
    (net (code "15") (name "/PWR_GPU_ON") (class "Default")
      (node (ref "R287") (pin "1") (pinfunction "1_1") (pintype "passive"))
    )
    (net (code "16") (name "/PWR_GPU_OVD") (class "Default")
      (node (ref "R155") (pin "1") (pinfunction "1_1") (pintype "passive"))
      (node (ref "R295") (pin "1") (pinfunction "1_1") (pintype "passive"))
    )
    (net (code "17") (name "/PWR_LP") (class "Default")
      (node (ref "R22") (pin "1") (pinfunction "1_1") (pintype "passive"))
      (node (ref "R278") (pin "1") (pinfunction "1_1") (pintype "passive"))
      (node (ref "R286") (pin "1") (pinfunction "1_1") (pintype "passive"))
    )
    (net (code "18") (name "/PWR_ON") (class "Default")
      (node (ref "R273") (pin "1") (pinfunction "1_1") (pintype "passive"))
    )
    (net (code "19") (name "/PWR_ONRST") (class "Default")
      (node (ref "R282") (pin "1") (pinfunction "1_1") (pintype "passive"))
    )
    (net (code "20") (name "5V_STLK") (class "Default")
      (node (ref "JP4") (pin "1") (pinfunction "COMMON_1") (pintype "passive"))
    )
    (net (code "21") (name "5V_VIN") (class "Default")
      (node (ref "JP3") (pin "1") (pinfunction "COMMON_1") (pintype "passive"))
      (node (ref "JP4") (pin "2") (pinfunction "NO_2") (pintype "passive"))
      (node (ref "R154") (pin "1") (pinfunction "1_1") (pintype "passive"))
      (node (ref "R208") (pin "1") (pinfunction "1_1") (pintype "passive"))
      (node (ref "R224") (pin "1") (pinfunction "1_1") (pintype "passive"))
      (node (ref "R225") (pin "2") (pinfunction "2_2") (pintype "passive"))
      (node (ref "R285") (pin "1") (pinfunction "1_1") (pintype "passive"))
      (node (ref "R93") (pin "2") (pinfunction "2_2") (pintype "passive"))
    )
    (net (code "22") (name "GND") (class "Default")
      (node (ref "C106") (pin "1") (pinfunction "1_1") (pintype "passive"))
      (node (ref "C109") (pin "1") (pinfunction "1_1") (pintype "passive"))
      (node (ref "C110") (pin "1") (pinfunction "1_1") (pintype "passive"))
      (node (ref "C120") (pin "1") (pinfunction "1_1") (pintype "passive"))
      (node (ref "C123") (pin "1") (pinfunction "1_1") (pintype "passive"))
      (node (ref "C128") (pin "1") (pinfunction "1_1") (pintype "passive"))
      (node (ref "C135") (pin "1") (pinfunction "1_1") (pintype "passive"))
      (node (ref "C136") (pin "1") (pinfunction "1_1") (pintype "passive"))
      (node (ref "C137") (pin "1") (pinfunction "1_1") (pintype "passive"))
      (node (ref "C138") (pin "1") (pinfunction "1_1") (pintype "passive"))
      (node (ref "C140") (pin "1") (pinfunction "1_1") (pintype "passive"))
      (node (ref "C3") (pin "1") (pinfunction "1_1") (pintype "passive"))
      (node (ref "C307") (pin "1") (pinfunction "1_1") (pintype "passive"))
      (node (ref "C308") (pin "1") (pinfunction "1_1") (pintype "passive"))
      (node (ref "C309") (pin "1") (pinfunction "1_1") (pintype "passive"))
      (node (ref "C310") (pin "1") (pinfunction "1_1") (pintype "passive"))
      (node (ref "C311") (pin "1") (pinfunction "1_1") (pintype "passive"))
      (node (ref "C312") (pin "1") (pinfunction "1_1") (pintype "passive"))
      (node (ref "C313") (pin "1") (pinfunction "1_1") (pintype "passive"))
      (node (ref "C314") (pin "1") (pinfunction "1_1") (pintype "passive"))
      (node (ref "C315") (pin "1") (pinfunction "1_1") (pintype "passive"))
      (node (ref "C316") (pin "1") (pinfunction "1_1") (pintype "passive"))
      (node (ref "C317") (pin "1") (pinfunction "1_1") (pintype "passive"))
      (node (ref "C318") (pin "1") (pinfunction "1_1") (pintype "passive"))
      (node (ref "C319") (pin "1") (pinfunction "1_1") (pintype "passive"))
      (node (ref "C320") (pin "1") (pinfunction "1_1") (pintype "passive"))
      (node (ref "C321") (pin "1") (pinfunction "1_1") (pintype "passive"))
      (node (ref "C322") (pin "1") (pinfunction "1_1") (pintype "passive"))
      (node (ref "C324") (pin "1") (pinfunction "1_1") (pintype "passive"))
      (node (ref "C325") (pin "1") (pinfunction "1_1") (pintype "passive"))
      (node (ref "C326") (pin "1") (pinfunction "1_1") (pintype "passive"))
      (node (ref "C327") (pin "1") (pinfunction "1_1") (pintype "passive"))
      (node (ref "C328") (pin "1") (pinfunction "1_1") (pintype "passive"))
      (node (ref "C329") (pin "1") (pinfunction "1_1") (pintype "passive"))
      (node (ref "C39") (pin "1") (pinfunction "1_1") (pintype "passive"))
      (node (ref "C4") (pin "1") (pinfunction "1_1") (pintype "passive"))
      (node (ref "C40") (pin "1") (pinfunction "1_1") (pintype "passive"))
      (node (ref "C42") (pin "2") (pinfunction "2_2") (pintype "passive"))
      (node (ref "C48") (pin "1") (pinfunction "1_1") (pintype "passive"))
      (node (ref "C49") (pin "1") (pinfunction "1_1") (pintype "passive"))
      (node (ref "C5") (pin "1") (pinfunction "1_1") (pintype "passive"))
      (node (ref "C6") (pin "1") (pinfunction "1_1") (pintype "passive"))
      (node (ref "C64") (pin "1") (pinfunction "1_1") (pintype "passive"))
      (node (ref "C7") (pin "1") (pinfunction "1_1") (pintype "passive"))
      (node (ref "C8") (pin "2") (pinfunction "2_2") (pintype "passive"))
      (node (ref "CN15") (pin "7") (pinfunction "7_7") (pintype "passive"))
      (node (ref "CN15") (pin "8") (pinfunction "8_8") (pintype "passive"))
      (node (ref "CN8") (pin "2") (pintype "passive"))
      (node (ref "CN8") (pin "3") (pintype "passive"))
      (node (ref "LD4") (pin "2") (pintype "passive"))
      (node (ref "Q7") (pin "2") (pinfunction "S_2") (pintype "passive"))
      (node (ref "Q8") (pin "2") (pinfunction "S_2") (pintype "passive"))
      (node (ref "Q9") (pin "2") (pinfunction "S_2") (pintype "passive"))
      (node (ref "R147") (pin "1") (pinfunction "1_1") (pintype "passive"))
      (node (ref "R155") (pin "2") (pinfunction "2_2") (pintype "passive"))
      (node (ref "R211") (pin "1") (pinfunction "1_1") (pintype "passive"))
      (node (ref "R275") (pin "1") (pinfunction "1_1") (pintype "passive"))
      (node (ref "R292") (pin "1") (pinfunction "1_1") (pintype "passive"))
      (node (ref "R293") (pin "1") (pinfunction "1_1") (pintype "passive"))
      (node (ref "R95") (pin "1") (pinfunction "1_1") (pintype "passive"))
      (node (ref "TP40") (pin "1") (pinfunction "1_1") (pintype "passive"))
      (node (ref "U2") (pin "C2") (pinfunction "GND_C2") (pintype "passive"))
      (node (ref "U30") (pin "C2") (pinfunction "GND_C2") (pintype "passive"))
      (node (ref "U37") (pin "C2") (pinfunction "GND_C2") (pintype "passive"))
      (node (ref "U38") (pin "16") (pinfunction "PGND_VPP_16") (pintype "passive"))
      (node (ref "U38") (pin "3") (pinfunction "AGND_3") (pintype "passive"))
      (node (ref "U38") (pin "9") (pinfunction "PGND_9") (pintype "passive"))
      (node (ref "U39") (pin "C2") (pinfunction "GND_C2") (pintype "passive"))
      (node (ref "U8") (pin "4") (pinfunction "GND_4") (pintype "passive"))
      (node (ref "U8") (pin "8") (pinfunction "PGND_8") (pintype "passive"))
    )
    (net (code "23") (name "Net-(C10-Pad2)") (class "Default")
      (node (ref "C10") (pin "2") (pinfunction "2_2") (pintype "passive"))
      (node (ref "LNK3") (pin "1") (pinfunction "1_1") (pintype "passive"))
      (node (ref "R274") (pin "2") (pinfunction "2_2") (pintype "passive"))
    )
    (net (code "24") (name "Net-(C31-Pad2)") (class "Default")
      (node (ref "C31") (pin "2") (pinfunction "2_2") (pintype "passive"))
      (node (ref "LNK2") (pin "2") (pinfunction "2_2") (pintype "passive"))
      (node (ref "R135") (pin "2") (pinfunction "2_2") (pintype "passive"))
    )
    (net (code "25") (name "Net-(C41-Pad2)") (class "Default")
      (node (ref "C41") (pin "2") (pinfunction "2_2") (pintype "passive"))
      (node (ref "R277") (pin "1") (pinfunction "1_1") (pintype "passive"))
    )
    (net (code "26") (name "Net-(C139-Pad2)") (class "Default")
      (node (ref "C139") (pin "2") (pinfunction "2_2") (pintype "passive"))
      (node (ref "LNK8") (pin "1") (pinfunction "1_1") (pintype "passive"))
      (node (ref "R210") (pin "2") (pinfunction "2_2") (pintype "passive"))
    )
    (net (code "27") (name "Net-(C330-Pad2)") (class "Default")
      (node (ref "C330") (pin "2") (pinfunction "2_2") (pintype "passive"))
      (node (ref "LNK10") (pin "1") (pinfunction "1_1") (pintype "passive"))
      (node (ref "R288") (pin "2") (pinfunction "2_2") (pintype "passive"))
    )
    (net (code "28") (name "Net-(JP3-NO)") (class "Default")
      (node (ref "C109") (pin "2") (pinfunction "2_2") (pintype "passive"))
      (node (ref "C110") (pin "2") (pinfunction "2_2") (pintype "passive"))
      (node (ref "C111") (pin "1") (pinfunction "1_1") (pintype "passive"))
      (node (ref "JP3") (pin "2") (pinfunction "NO_2") (pintype "passive"))
      (node (ref "L4") (pin "2") (pinfunction "2_2") (pintype "passive"))
      (node (ref "R12") (pin "1") (pinfunction "1_1") (pintype "passive"))
    )
    (net (code "29") (name "Net-(LD4-Pad1)") (class "Default")
      (node (ref "LD4") (pin "1") (pintype "passive"))
      (node (ref "R93") (pin "1") (pinfunction "1_1") (pintype "passive"))
    )
    (net (code "30") (name "Net-(Q7-D)") (class "Default")
      (node (ref "Q7") (pin "3") (pinfunction "D_3") (pintype "passive"))
      (node (ref "R148") (pin "1") (pinfunction "1_1") (pintype "passive"))
    )
    (net (code "31") (name "Net-(Q7-G)") (class "Default")
      (node (ref "Q7") (pin "1") (pinfunction "G_1") (pintype "passive"))
      (node (ref "R22") (pin "2") (pinfunction "2_2") (pintype "passive"))
    )
    (net (code "32") (name "Net-(Q8-D)") (class "Default")
      (node (ref "Q8") (pin "3") (pinfunction "D_3") (pintype "passive"))
      (node (ref "R276") (pin "1") (pinfunction "1_1") (pintype "passive"))
    )
    (net (code "33") (name "Net-(Q8-G)") (class "Default")
      (node (ref "Q8") (pin "1") (pinfunction "G_1") (pintype "passive"))
      (node (ref "R278") (pin "2") (pinfunction "2_2") (pintype "passive"))
    )
    (net (code "34") (name "Net-(Q9-D)") (class "Default")
      (node (ref "Q9") (pin "3") (pinfunction "D_3") (pintype "passive"))
      (node (ref "R294") (pin "1") (pinfunction "1_1") (pintype "passive"))
    )
    (net (code "35") (name "Net-(Q9-G)") (class "Default")
      (node (ref "Q9") (pin "1") (pinfunction "G_1") (pintype "passive"))
      (node (ref "R295") (pin "2") (pinfunction "2_2") (pintype "passive"))
    )
    (net (code "36") (name "Net-(U2-EN)") (class "Default")
      (node (ref "R209") (pin "2") (pinfunction "2_2") (pintype "passive"))
      (node (ref "U2") (pin "A1") (pinfunction "EN_A1") (pintype "passive"))
    )
    (net (code "37") (name "Net-(U2-FB)") (class "Default")
      (node (ref "C31") (pin "1") (pinfunction "1_1") (pintype "passive"))
      (node (ref "R135") (pin "1") (pinfunction "1_1") (pintype "passive"))
      (node (ref "R147") (pin "2") (pinfunction "2_2") (pintype "passive"))
      (node (ref "R148") (pin "2") (pinfunction "2_2") (pintype "passive"))
      (node (ref "U2") (pin "C1") (pinfunction "FB_C1") (pintype "passive"))
    )
    (net (code "38") (name "Net-(U2-PG)") (class "Default")
      (node (ref "TP21") (pin "1") (pinfunction "1_1") (pintype "passive"))
      (node (ref "U2") (pin "B1") (pinfunction "PG_B1") (pintype "passive"))
    )
    (net (code "39") (name "Net-(U2-SW)") (class "Default")
      (node (ref "L10") (pin "1") (pinfunction "1_1") (pintype "passive"))
      (node (ref "U2") (pin "B2") (pinfunction "SW_B2") (pintype "passive"))
    )
    (net (code "40") (name "Net-(U2-VIN)") (class "Default")
      (node (ref "C3") (pin "2") (pinfunction "2_2") (pintype "passive"))
      (node (ref "C4") (pin "2") (pinfunction "2_2") (pintype "passive"))
      (node (ref "R154") (pin "2") (pinfunction "2_2") (pintype "passive"))
      (node (ref "U2") (pin "A2") (pinfunction "VIN_A2") (pintype "passive"))
    )
    (net (code "41") (name "Net-(U8-EN)") (class "Default")
      (node (ref "C106") (pin "2") (pinfunction "2_2") (pintype "passive"))
      (node (ref "C40") (pin "2") (pinfunction "2_2") (pintype "passive"))
      (node (ref "C5") (pin "2") (pinfunction "2_2") (pintype "passive"))
      (node (ref "C64") (pin "2") (pinfunction "2_2") (pintype "passive"))
      (node (ref "C8") (pin "1") (pinfunction "1_1") (pintype "passive"))
      (node (ref "F1") (pin "2") (pinfunction "2_2") (pintype "passive"))
      (node (ref "U8") (pin "1") (pinfunction "VINA_1") (pintype "passive"))
      (node (ref "U8") (pin "2") (pinfunction "EN_2") (pintype "passive"))
      (node (ref "U8") (pin "6") (pinfunction "VINSW_6") (pintype "passive"))
    )
    (net (code "42") (name "Net-(U8-FB)") (class "Default")
      (node (ref "C111") (pin "2") (pinfunction "2_2") (pintype "passive"))
      (node (ref "R12") (pin "2") (pinfunction "2_2") (pintype "passive"))
      (node (ref "R95") (pin "2") (pinfunction "2_2") (pintype "passive"))
      (node (ref "U8") (pin "3") (pinfunction "FB_3") (pintype "passive"))
    )
    (net (code "43") (name "Net-(U8-SW)") (class "Default")
      (node (ref "L4") (pin "1") (pinfunction "1_1") (pintype "passive"))
      (node (ref "U8") (pin "7") (pinfunction "SW_7") (pintype "passive"))
    )
    (net (code "44") (name "Net-(U30-EN)") (class "Default")
      (node (ref "C136") (pin "2") (pinfunction "2_2") (pintype "passive"))
      (node (ref "C48") (pin "2") (pinfunction "2_2") (pintype "passive"))
      (node (ref "R208") (pin "2") (pinfunction "2_2") (pintype "passive"))
      (node (ref "U30") (pin "A1") (pinfunction "EN_A1") (pintype "passive"))
      (node (ref "U30") (pin "A2") (pinfunction "VIN_A2") (pintype "passive"))
    )
    (net (code "45") (name "Net-(U30-FB)") (class "Default")
      (node (ref "C139") (pin "1") (pinfunction "1_1") (pintype "passive"))
      (node (ref "R210") (pin "1") (pinfunction "1_1") (pintype "passive"))
      (node (ref "R211") (pin "2") (pinfunction "2_2") (pintype "passive"))
      (node (ref "U30") (pin "C1") (pinfunction "FB_C1") (pintype "passive"))
    )
    (net (code "46") (name "Net-(U30-PG)") (class "Default")
      (node (ref "R269") (pin "2") (pinfunction "2_2") (pintype "passive"))
      (node (ref "U30") (pin "B1") (pinfunction "PG_B1") (pintype "passive"))
    )
    (net (code "47") (name "Net-(U30-SW)") (class "Default")
      (node (ref "L13") (pin "1") (pinfunction "1_1") (pintype "passive"))
      (node (ref "U30") (pin "B2") (pinfunction "SW_B2") (pintype "passive"))
    )
    (net (code "48") (name "Net-(U37-EN)") (class "Default")
      (node (ref "R273") (pin "2") (pinfunction "2_2") (pintype "passive"))
      (node (ref "U37") (pin "A1") (pinfunction "EN_A1") (pintype "passive"))
    )
    (net (code "49") (name "Net-(U37-FB)") (class "Default")
      (node (ref "C10") (pin "1") (pinfunction "1_1") (pintype "passive"))
      (node (ref "R274") (pin "1") (pinfunction "1_1") (pintype "passive"))
      (node (ref "R275") (pin "2") (pinfunction "2_2") (pintype "passive"))
      (node (ref "R276") (pin "2") (pinfunction "2_2") (pintype "passive"))
      (node (ref "U37") (pin "C1") (pinfunction "FB_C1") (pintype "passive"))
    )
    (net (code "50") (name "Net-(U37-PG)") (class "Default")
      (node (ref "TP13") (pin "1") (pinfunction "1_1") (pintype "passive"))
      (node (ref "U37") (pin "B1") (pinfunction "PG_B1") (pintype "passive"))
    )
    (net (code "51") (name "Net-(U37-SW)") (class "Default")
      (node (ref "L1") (pin "1") (pinfunction "1_1") (pintype "passive"))
      (node (ref "U37") (pin "B2") (pinfunction "SW_B2") (pintype "passive"))
    )
    (net (code "52") (name "Net-(U37-VIN)") (class "Default")
      (node (ref "C6") (pin "2") (pinfunction "2_2") (pintype "passive"))
      (node (ref "C7") (pin "2") (pinfunction "2_2") (pintype "passive"))
      (node (ref "R224") (pin "2") (pinfunction "2_2") (pintype "passive"))
      (node (ref "U37") (pin "A2") (pinfunction "VIN_A2") (pintype "passive"))
    )
    (net (code "53") (name "Net-(U38-BST)") (class "Default")
      (node (ref "C41") (pin "1") (pinfunction "1_1") (pintype "passive"))
      (node (ref "U38") (pin "18") (pinfunction "BST_18") (pintype "passive"))
    )
    (net (code "54") (name "Net-(U38-PGOOD)") (class "Default")
      (node (ref "R34") (pin "1") (pinfunction "1_1") (pintype "passive"))
      (node (ref "U38") (pin "8") (pinfunction "PGOOD_8") (pintype "passive"))
    )
    (net (code "55") (name "Net-(U38-PIN_VPP)") (class "Default")
      (node (ref "C310") (pin "2") (pinfunction "2_2") (pintype "passive"))
      (node (ref "C316") (pin "2") (pinfunction "2_2") (pintype "passive"))
      (node (ref "C317") (pin "2") (pinfunction "2_2") (pintype "passive"))
      (node (ref "C318") (pin "2") (pinfunction "2_2") (pintype "passive"))
      (node (ref "C39") (pin "2") (pinfunction "2_2") (pintype "passive"))
      (node (ref "R225") (pin "1") (pinfunction "1_1") (pintype "passive"))
      (node (ref "R34") (pin "2") (pinfunction "2_2") (pintype "passive"))
      (node (ref "U38") (pin "13") (pinfunction "VCC_5V_13") (pintype "passive"))
      (node (ref "U38") (pin "14") (pinfunction "PIN_VPP_14") (pintype "passive"))
      (node (ref "U38") (pin "7") (pinfunction "PVIN_7") (pintype "passive"))
    )
    (net (code "56") (name "Net-(U38-SLP_S4)") (class "Default")
      (node (ref "R281") (pin "2") (pinfunction "2_2") (pintype "passive"))
      (node (ref "R282") (pin "2") (pinfunction "2_2") (pintype "passive"))
      (node (ref "U38") (pin "11") (pinfunction "SLP_S4_11") (pintype "passive"))
    )
    (net (code "57") (name "Net-(U38-SW)") (class "Default")
      (node (ref "L15") (pin "1") (pinfunction "1_1") (pintype "passive"))
      (node (ref "R277") (pin "2") (pinfunction "2_2") (pintype "passive"))
      (node (ref "U38") (pin "17") (pinfunction "SW_17") (pintype "passive"))
    )
    (net (code "58") (name "Net-(U38-SW_VPP)") (class "Default")
      (node (ref "L19") (pin "1") (pinfunction "1_1") (pintype "passive"))
      (node (ref "U38") (pin "15") (pinfunction "SW_VPP_15") (pintype "passive"))
    )
    (net (code "59") (name "Net-(U38-VDDQSNS)") (class "Default")
      (node (ref "LNK7") (pin "1") (pinfunction "1_1") (pintype "passive"))
      (node (ref "U38") (pin "5") (pinfunction "VDDQSNS_5") (pintype "passive"))
    )
    (net (code "60") (name "Net-(U38-VTTCNTL)") (class "Default")
      (node (ref "R286") (pin "2") (pinfunction "2_2") (pintype "passive"))
      (node (ref "U38") (pin "10") (pinfunction "VTTCNTL_10") (pintype "passive"))
    )
    (net (code "61") (name "Net-(U38-VTTREF)") (class "Default")
      (node (ref "C42") (pin "1") (pinfunction "1_1") (pintype "passive"))
      (node (ref "R283") (pin "1") (pinfunction "1_1") (pintype "passive"))
      (node (ref "U38") (pin "6") (pinfunction "VTTREF_6") (pintype "passive"))
    )
    (net (code "62") (name "Net-(U38-VTTSNS)") (class "Default")
      (node (ref "R279") (pin "1") (pinfunction "1_1") (pintype "passive"))
      (node (ref "U38") (pin "4") (pinfunction "VTTSNS_4") (pintype "passive"))
    )
    (net (code "63") (name "Net-(U39-EN)") (class "Default")
      (node (ref "R287") (pin "2") (pinfunction "2_2") (pintype "passive"))
      (node (ref "R292") (pin "2") (pinfunction "2_2") (pintype "passive"))
      (node (ref "U39") (pin "A1") (pinfunction "EN_A1") (pintype "passive"))
    )
    (net (code "64") (name "Net-(U39-FB)") (class "Default")
      (node (ref "C330") (pin "1") (pinfunction "1_1") (pintype "passive"))
      (node (ref "R288") (pin "1") (pinfunction "1_1") (pintype "passive"))
      (node (ref "R293") (pin "2") (pinfunction "2_2") (pintype "passive"))
      (node (ref "R294") (pin "2") (pinfunction "2_2") (pintype "passive"))
      (node (ref "U39") (pin "C1") (pinfunction "FB_C1") (pintype "passive"))
    )
    (net (code "65") (name "Net-(U39-PG)") (class "Default")
      (node (ref "TP14") (pin "1") (pinfunction "1_1") (pintype "passive"))
      (node (ref "U39") (pin "B1") (pinfunction "PG_B1") (pintype "passive"))
    )
    (net (code "66") (name "Net-(U39-SW)") (class "Default")
      (node (ref "L7") (pin "1") (pinfunction "1_1") (pintype "passive"))
      (node (ref "U39") (pin "B2") (pinfunction "SW_B2") (pintype "passive"))
    )
    (net (code "67") (name "Net-(U39-VIN)") (class "Default")
      (node (ref "C324") (pin "2") (pinfunction "2_2") (pintype "passive"))
      (node (ref "C325") (pin "2") (pinfunction "2_2") (pintype "passive"))
      (node (ref "R285") (pin "2") (pinfunction "2_2") (pintype "passive"))
      (node (ref "U39") (pin "A2") (pinfunction "VIN_A2") (pintype "passive"))
    )
    (net (code "68") (name "VDDCORE") (class "Default")
      (node (ref "LNK1") (pin "1") (pinfunction "1_1") (pintype "passive"))
      (node (ref "LNK3") (pin "2") (pinfunction "2_2") (pintype "passive"))
      (node (ref "R27") (pin "2") (pinfunction "2_2") (pintype "passive"))
    )
    (net (code "69") (name "VDDCPU") (class "Default")
      (node (ref "LNK2") (pin "1") (pinfunction "1_1") (pintype "passive"))
      (node (ref "LNK4") (pin "1") (pinfunction "1_1") (pintype "passive"))
      (node (ref "R134") (pin "2") (pinfunction "2_2") (pintype "passive"))
    )
    (net (code "70") (name "VDDGPU") (class "Default")
      (node (ref "LNK10") (pin "2") (pinfunction "2_2") (pintype "passive"))
      (node (ref "LNK9") (pin "1") (pinfunction "1_1") (pintype "passive"))
      (node (ref "R284") (pin "2") (pinfunction "2_2") (pintype "passive"))
    )
    (net (code "71") (name "VDDIO") (class "Default")
      (node (ref "LNK6") (pin "2") (pinfunction "2_2") (pintype "passive"))
      (node (ref "LNK8") (pin "2") (pinfunction "2_2") (pintype "passive"))
      (node (ref "R272") (pin "2") (pinfunction "2_2") (pintype "passive"))
    )
    (net (code "72") (name "VDD_DDR") (class "Default")
      (node (ref "C321") (pin "2") (pinfunction "2_2") (pintype "passive"))
      (node (ref "LNK5") (pin "2") (pinfunction "2_2") (pintype "passive"))
      (node (ref "LNK7") (pin "2") (pinfunction "2_2") (pintype "passive"))
      (node (ref "R226") (pin "2") (pinfunction "2_2") (pintype "passive"))
      (node (ref "U38") (pin "1") (pinfunction "VLDOIN_1") (pintype "passive"))
    )
    (net (code "73") (name "VIN_JACK") (class "Default")
      (node (ref "CN8") (pin "1") (pintype "passive"))
      (node (ref "F1") (pin "1") (pinfunction "1_1") (pintype "passive"))
    )
    (net (code "74") (name "VPP_DDR") (class "Default")
      (node (ref "C319") (pin "2") (pinfunction "2_2") (pintype "passive"))
      (node (ref "C320") (pin "2") (pinfunction "2_2") (pintype "passive"))
      (node (ref "L19") (pin "2") (pinfunction "2_2") (pintype "passive"))
      (node (ref "U38") (pin "12") (pinfunction "VPPSNS_12") (pintype "passive"))
    )
    (net (code "75") (name "VREF_DDR") (class "Default")
      (node (ref "R283") (pin "2") (pinfunction "2_2") (pintype "passive"))
    )
    (net (code "76") (name "VTT_DDR") (class "Default")
      (node (ref "C322") (pin "2") (pinfunction "2_2") (pintype "passive"))
      (node (ref "R279") (pin "2") (pinfunction "2_2") (pintype "passive"))
      (node (ref "U38") (pin "2") (pinfunction "VTT_2") (pintype "passive"))
    )
    (net (code "77") (name "unconnected-(CN15-Pad13)") (class "Default")
      (node (ref "CN15") (pin "13") (pinfunction "13_13") (pintype "passive+no_connect"))
    )
    (net (code "78") (name "unconnected-(CN15-Pad14)") (class "Default")
      (node (ref "CN15") (pin "14") (pinfunction "14_14") (pintype "passive+no_connect"))
    )
    (net (code "79") (name "unconnected-(U8-NC-Pad5)") (class "Default")
      (node (ref "U8") (pin "5") (pinfunction "NC_5") (pintype "passive+no_connect"))
    )
  )
)
